# POV.net
KiCad netlist of a schematic drawn in EAGLE
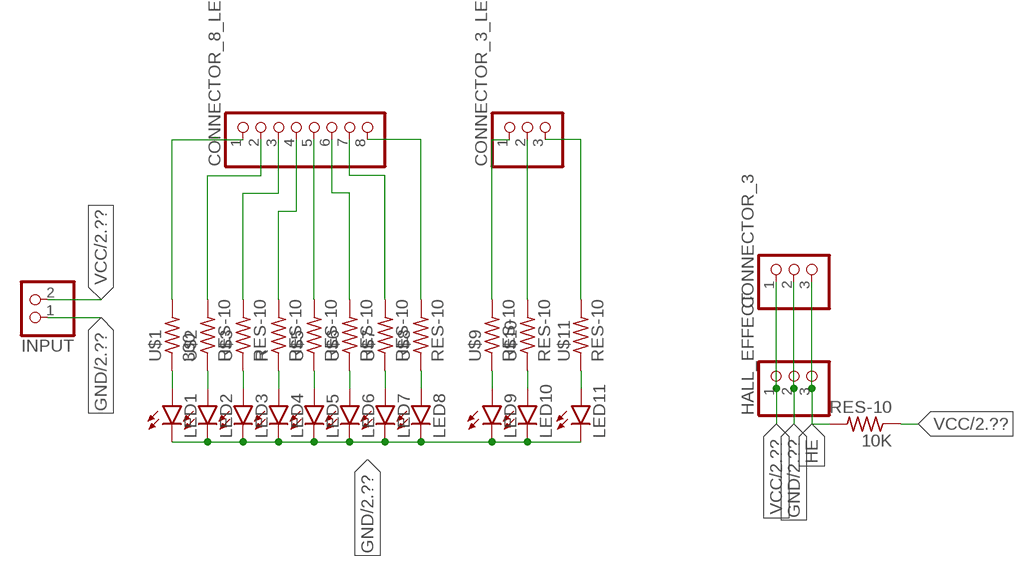
[diagram p0: schematic, sheet 1]
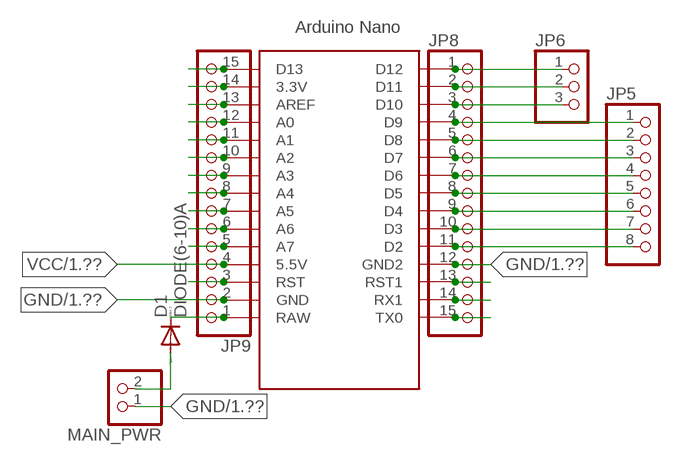
[diagram p1: schematic, sheet 2]

(export (version "E")
  (design (tool "Eeschema 10.0.6"))
  (components
    (comp (ref "D1")
      (value "DIODE(6-10)A")
      (footprint "eagle-import:DO201-15")
      (libsource (lib "eagle-import") (part "DIODE(6-10)A"))
    )
    (comp (ref "JP5")
      (value "PINHD-1X8")
      (footprint "eagle-import:1X08")
      (libsource (lib "eagle-import") (part "PINHD-1X8"))
    )
    (comp (ref "JP6")
      (value "PINHD-1X3")
      (footprint "eagle-import:1X03")
      (libsource (lib "eagle-import") (part "PINHD-1X3"))
    )
    (comp (ref "JP8")
      (value "PINHD-1X15")
      (footprint "eagle-import:1X15")
      (libsource (lib "eagle-import") (part "PINHD-1X15"))
    )
    (comp (ref "JP9")
      (value "PINHD-1X15")
      (footprint "eagle-import:1X15")
      (libsource (lib "eagle-import") (part "PINHD-1X15"))
    )
    (comp (ref "MAIN_PWR")
      (value "PINHD-1X2")
      (footprint "eagle-import:1X02")
      (libsource (lib "eagle-import") (part "PINHD-1X2"))
    )
    (comp (ref "U$12")
      (value "ARDUINO_NANO")
      (footprint "eagle-import:NANO")
      (libsource (lib "eagle-import") (part "ARDUINO_NANO"))
    )
    (comp (ref "10K")
      (value "RES-10")
      (footprint "eagle-import:0207_10")
      (libsource (lib "eagle-import") (part "RES-10"))
    )
    (comp (ref "CONNECTOR_3")
      (value "PINHD-1X3")
      (footprint "eagle-import:1X03")
      (libsource (lib "eagle-import") (part "pinhead_325_PINHD-1X3"))
    )
    (comp (ref "CONNECTOR_3_LED")
      (value "PINHD-1X3")
      (footprint "eagle-import:1X03")
      (libsource (lib "eagle-import") (part "pinhead_325_PINHD-1X3"))
    )
    (comp (ref "CONNECTOR_8_LED")
      (value "PINHD-1X8")
      (footprint "eagle-import:1X08")
      (libsource (lib "eagle-import") (part "pinhead_325_PINHD-1X8"))
    )
    (comp (ref "HALL_EFFECT")
      (value "PINHD-1X3")
      (footprint "eagle-import:1X03")
      (libsource (lib "eagle-import") (part "pinhead_325_PINHD-1X3"))
    )
    (comp (ref "INPUT")
      (value "PINHD-1X2")
      (footprint "eagle-import:1X02")
      (libsource (lib "eagle-import") (part "pinhead_325_PINHD-1X2"))
    )
    (comp (ref "LED1")
      (value "LED5MM")
      (footprint "eagle-import:LED5MM")
      (libsource (lib "eagle-import") (part "LED5MM"))
    )
    (comp (ref "LED2")
      (value "LED5MM")
      (footprint "eagle-import:LED5MM")
      (libsource (lib "eagle-import") (part "LED5MM"))
    )
    (comp (ref "LED3")
      (value "LED5MM")
      (footprint "eagle-import:LED5MM")
      (libsource (lib "eagle-import") (part "LED5MM"))
    )
    (comp (ref "LED4")
      (value "LED5MM")
      (footprint "eagle-import:LED5MM")
      (libsource (lib "eagle-import") (part "LED5MM"))
    )
    (comp (ref "LED5")
      (value "LED5MM")
      (footprint "eagle-import:LED5MM")
      (libsource (lib "eagle-import") (part "LED5MM"))
    )
    (comp (ref "LED6")
      (value "LED5MM")
      (footprint "eagle-import:LED5MM")
      (libsource (lib "eagle-import") (part "LED5MM"))
    )
    (comp (ref "LED7")
      (value "LED5MM")
      (footprint "eagle-import:LED5MM")
      (libsource (lib "eagle-import") (part "LED5MM"))
    )
    (comp (ref "LED8")
      (value "LED5MM")
      (footprint "eagle-import:LED5MM")
      (libsource (lib "eagle-import") (part "LED5MM"))
    )
    (comp (ref "LED9")
      (value "LED5MM")
      (footprint "eagle-import:LED5MM")
      (libsource (lib "eagle-import") (part "LED5MM"))
    )
    (comp (ref "LED10")
      (value "LED5MM")
      (footprint "eagle-import:LED5MM")
      (libsource (lib "eagle-import") (part "LED5MM"))
    )
    (comp (ref "LED11")
      (value "LED5MM")
      (footprint "eagle-import:LED5MM")
      (libsource (lib "eagle-import") (part "LED5MM"))
    )
    (comp (ref "R")
      (value "RES-10")
      (footprint "eagle-import:0207_10")
      (libsource (lib "eagle-import") (part "RES-10"))
    )
    (comp (ref "U$1")
      (value "330")
      (footprint "eagle-import:0207_10")
      (libsource (lib "eagle-import") (part "RES-10"))
    )
    (comp (ref "U$2")
      (value "RES-10")
      (footprint "eagle-import:0207_10")
      (libsource (lib "eagle-import") (part "RES-10"))
    )
    (comp (ref "U$3")
      (value "RES-10")
      (footprint "eagle-import:0207_10")
      (libsource (lib "eagle-import") (part "RES-10"))
    )
    (comp (ref "U$5")
      (value "RES-10")
      (footprint "eagle-import:0207_10")
      (libsource (lib "eagle-import") (part "RES-10"))
    )
    (comp (ref "U$6")
      (value "RES-10")
      (footprint "eagle-import:0207_10")
      (libsource (lib "eagle-import") (part "RES-10"))
    )
    (comp (ref "U$7")
      (value "RES-10")
      (footprint "eagle-import:0207_10")
      (libsource (lib "eagle-import") (part "RES-10"))
    )
    (comp (ref "U$8")
      (value "RES-10")
      (footprint "eagle-import:0207_10")
      (libsource (lib "eagle-import") (part "RES-10"))
    )
    (comp (ref "U$9")
      (value "RES-10")
      (footprint "eagle-import:0207_10")
      (libsource (lib "eagle-import") (part "RES-10"))
    )
    (comp (ref "U$10")
      (value "RES-10")
      (footprint "eagle-import:0207_10")
      (libsource (lib "eagle-import") (part "RES-10"))
    )
    (comp (ref "U$11")
      (value "RES-10")
      (footprint "eagle-import:0207_10")
      (libsource (lib "eagle-import") (part "RES-10"))
    )
  )
  (nets
    (net (code "1") (name "GND") (class "Default")
      (node (ref "CONNECTOR_3") (pin "2") (pinfunction "2_2") (pintype "passive"))
      (node (ref "HALL_EFFECT") (pin "2") (pinfunction "2_2") (pintype "passive"))
      (node (ref "INPUT") (pin "1") (pinfunction "1_1") (pintype "passive"))
      (node (ref "JP8") (pin "12") (pinfunction "12_12") (pintype "passive"))
      (node (ref "JP9") (pin "2") (pinfunction "2_2") (pintype "passive"))
      (node (ref "LED1") (pin "K") (pinfunction "C_K") (pintype "passive"))
      (node (ref "LED10") (pin "K") (pinfunction "C_K") (pintype "passive"))
      (node (ref "LED11") (pin "K") (pinfunction "C_K") (pintype "passive"))
      (node (ref "LED2") (pin "K") (pinfunction "C_K") (pintype "passive"))
      (node (ref "LED3") (pin "K") (pinfunction "C_K") (pintype "passive"))
      (node (ref "LED4") (pin "K") (pinfunction "C_K") (pintype "passive"))
      (node (ref "LED5") (pin "K") (pinfunction "C_K") (pintype "passive"))
      (node (ref "LED6") (pin "K") (pinfunction "C_K") (pintype "passive"))
      (node (ref "LED7") (pin "K") (pinfunction "C_K") (pintype "passive"))
      (node (ref "LED8") (pin "K") (pinfunction "C_K") (pintype "passive"))
      (node (ref "LED9") (pin "K") (pinfunction "C_K") (pintype "passive"))
      (node (ref "MAIN_PWR") (pin "1") (pinfunction "1_1") (pintype "passive"))
      (node (ref "U$12") (pin "GND") (pinfunction "GND_GND") (pintype "bidirectional"))
      (node (ref "U$12") (pin "GND1") (pinfunction "GND2_GND1") (pintype "bidirectional"))
    )
    (net (code "2") (name "HE") (class "Default")
      (node (ref "10K") (pin "2") (pinfunction "2_2") (pintype "passive"))
      (node (ref "CONNECTOR_3") (pin "3") (pinfunction "3_3") (pintype "passive"))
      (node (ref "HALL_EFFECT") (pin "3") (pinfunction "3_3") (pintype "passive"))
    )
    (net (code "3") (name "Net-(CONNECTOR_3_LED-Pad1)") (class "Default")
      (node (ref "CONNECTOR_3_LED") (pin "1") (pinfunction "1_1") (pintype "passive"))
      (node (ref "U$9") (pin "2") (pinfunction "2_2") (pintype "passive"))
    )
    (net (code "4") (name "Net-(CONNECTOR_3_LED-Pad2)") (class "Default")
      (node (ref "CONNECTOR_3_LED") (pin "2") (pinfunction "2_2") (pintype "passive"))
      (node (ref "U$10") (pin "2") (pinfunction "2_2") (pintype "passive"))
    )
    (net (code "5") (name "Net-(CONNECTOR_3_LED-Pad3)") (class "Default")
      (node (ref "CONNECTOR_3_LED") (pin "3") (pinfunction "3_3") (pintype "passive"))
      (node (ref "U$11") (pin "2") (pinfunction "2_2") (pintype "passive"))
    )
    (net (code "6") (name "Net-(CONNECTOR_8_LED-Pad1)") (class "Default")
      (node (ref "CONNECTOR_8_LED") (pin "1") (pinfunction "1_1") (pintype "passive"))
      (node (ref "U$1") (pin "2") (pinfunction "2_2") (pintype "passive"))
    )
    (net (code "7") (name "Net-(CONNECTOR_8_LED-Pad2)") (class "Default")
      (node (ref "CONNECTOR_8_LED") (pin "2") (pinfunction "2_2") (pintype "passive"))
      (node (ref "U$2") (pin "2") (pinfunction "2_2") (pintype "passive"))
    )
    (net (code "8") (name "Net-(CONNECTOR_8_LED-Pad3)") (class "Default")
      (node (ref "CONNECTOR_8_LED") (pin "3") (pinfunction "3_3") (pintype "passive"))
      (node (ref "U$3") (pin "2") (pinfunction "2_2") (pintype "passive"))
    )
    (net (code "9") (name "Net-(CONNECTOR_8_LED-Pad4)") (class "Default")
      (node (ref "CONNECTOR_8_LED") (pin "4") (pinfunction "4_4") (pintype "passive"))
      (node (ref "R") (pin "2") (pinfunction "2_2") (pintype "passive"))
    )
    (net (code "10") (name "Net-(CONNECTOR_8_LED-Pad5)") (class "Default")
      (node (ref "CONNECTOR_8_LED") (pin "5") (pinfunction "5_5") (pintype "passive"))
      (node (ref "U$5") (pin "2") (pinfunction "2_2") (pintype "passive"))
    )
    (net (code "11") (name "Net-(CONNECTOR_8_LED-Pad6)") (class "Default")
      (node (ref "CONNECTOR_8_LED") (pin "6") (pinfunction "6_6") (pintype "passive"))
      (node (ref "U$6") (pin "2") (pinfunction "2_2") (pintype "passive"))
    )
    (net (code "12") (name "Net-(CONNECTOR_8_LED-Pad7)") (class "Default")
      (node (ref "CONNECTOR_8_LED") (pin "7") (pinfunction "7_7") (pintype "passive"))
      (node (ref "U$7") (pin "2") (pinfunction "2_2") (pintype "passive"))
    )
    (net (code "13") (name "Net-(CONNECTOR_8_LED-Pad8)") (class "Default")
      (node (ref "CONNECTOR_8_LED") (pin "8") (pinfunction "8_8") (pintype "passive"))
      (node (ref "U$8") (pin "2") (pinfunction "2_2") (pintype "passive"))
    )
    (net (code "14") (name "Net-(D1-PadA)") (class "Default")
      (node (ref "D1") (pin "A") (pinfunction "A_A") (pintype "passive"))
      (node (ref "MAIN_PWR") (pin "2") (pinfunction "2_2") (pintype "passive"))
    )
    (net (code "15") (name "Net-(D1-PadC)") (class "Default")
      (node (ref "D1") (pin "C") (pinfunction "C_C") (pintype "passive"))
      (node (ref "JP9") (pin "1") (pinfunction "1_1") (pintype "passive"))
      (node (ref "U$12") (pin "RAW") (pinfunction "RAW_RAW") (pintype "bidirectional"))
    )
    (net (code "16") (name "Net-(JP5-Pad1)") (class "Default")
      (node (ref "JP5") (pin "1") (pinfunction "1_1") (pintype "passive"))
      (node (ref "JP8") (pin "4") (pinfunction "4_4") (pintype "passive"))
      (node (ref "U$12") (pin "D9") (pinfunction "D9_D9") (pintype "bidirectional"))
    )
    (net (code "17") (name "Net-(JP5-Pad2)") (class "Default")
      (node (ref "JP5") (pin "2") (pinfunction "2_2") (pintype "passive"))
      (node (ref "JP8") (pin "5") (pinfunction "5_5") (pintype "passive"))
      (node (ref "U$12") (pin "D8") (pinfunction "D8_D8") (pintype "bidirectional"))
    )
    (net (code "18") (name "Net-(JP5-Pad3)") (class "Default")
      (node (ref "JP5") (pin "3") (pinfunction "3_3") (pintype "passive"))
      (node (ref "JP8") (pin "6") (pinfunction "6_6") (pintype "passive"))
      (node (ref "U$12") (pin "D7") (pinfunction "D7_D7") (pintype "bidirectional"))
    )
    (net (code "19") (name "Net-(JP5-Pad4)") (class "Default")
      (node (ref "JP5") (pin "4") (pinfunction "4_4") (pintype "passive"))
      (node (ref "JP8") (pin "7") (pinfunction "7_7") (pintype "passive"))
      (node (ref "U$12") (pin "D6") (pinfunction "D6_D6") (pintype "bidirectional"))
    )
    (net (code "20") (name "Net-(JP5-Pad5)") (class "Default")
      (node (ref "JP5") (pin "5") (pinfunction "5_5") (pintype "passive"))
      (node (ref "JP8") (pin "8") (pinfunction "8_8") (pintype "passive"))
      (node (ref "U$12") (pin "D5") (pinfunction "D5_D5") (pintype "bidirectional"))
    )
    (net (code "21") (name "Net-(JP5-Pad6)") (class "Default")
      (node (ref "JP5") (pin "6") (pinfunction "6_6") (pintype "passive"))
      (node (ref "JP8") (pin "9") (pinfunction "9_9") (pintype "passive"))
      (node (ref "U$12") (pin "D4") (pinfunction "D4_D4") (pintype "bidirectional"))
    )
    (net (code "22") (name "Net-(JP5-Pad7)") (class "Default")
      (node (ref "JP5") (pin "7") (pinfunction "7_7") (pintype "passive"))
      (node (ref "JP8") (pin "10") (pinfunction "10_10") (pintype "passive"))
      (node (ref "U$12") (pin "D3") (pinfunction "D3_D3") (pintype "bidirectional"))
    )
    (net (code "23") (name "Net-(JP5-Pad8)") (class "Default")
      (node (ref "JP5") (pin "8") (pinfunction "8_8") (pintype "passive"))
      (node (ref "JP8") (pin "11") (pinfunction "11_11") (pintype "passive"))
      (node (ref "U$12") (pin "D2") (pinfunction "D2_D2") (pintype "bidirectional"))
    )
    (net (code "24") (name "Net-(JP6-Pad1)") (class "Default")
      (node (ref "JP6") (pin "1") (pinfunction "1_1") (pintype "passive"))
      (node (ref "JP8") (pin "1") (pinfunction "1_1") (pintype "passive"))
      (node (ref "U$12") (pin "D12") (pinfunction "D12_D12") (pintype "bidirectional"))
    )
    (net (code "25") (name "Net-(JP6-Pad2)") (class "Default")
      (node (ref "JP6") (pin "2") (pinfunction "2_2") (pintype "passive"))
      (node (ref "JP8") (pin "2") (pinfunction "2_2") (pintype "passive"))
      (node (ref "U$12") (pin "D11") (pinfunction "D11_D11") (pintype "bidirectional"))
    )
    (net (code "26") (name "Net-(JP6-Pad3)") (class "Default")
      (node (ref "JP6") (pin "3") (pinfunction "3_3") (pintype "passive"))
      (node (ref "JP8") (pin "3") (pinfunction "3_3") (pintype "passive"))
      (node (ref "U$12") (pin "D10") (pinfunction "D10_D10") (pintype "bidirectional"))
    )
    (net (code "27") (name "Net-(JP8-Pad13)") (class "Default")
      (node (ref "JP8") (pin "13") (pinfunction "13_13") (pintype "passive"))
      (node (ref "U$12") (pin "RST1") (pinfunction "RST1_RST1") (pintype "bidirectional"))
    )
    (net (code "28") (name "Net-(JP8-Pad14)") (class "Default")
      (node (ref "JP8") (pin "14") (pinfunction "14_14") (pintype "passive"))
      (node (ref "U$12") (pin "RX1") (pinfunction "RX1_RX1") (pintype "bidirectional"))
    )
    (net (code "29") (name "Net-(JP8-Pad15)") (class "Default")
      (node (ref "JP8") (pin "15") (pinfunction "15_15") (pintype "passive"))
      (node (ref "U$12") (pin "TX0") (pinfunction "TX0_TX0") (pintype "bidirectional"))
    )
    (net (code "30") (name "Net-(JP9-Pad3)") (class "Default")
      (node (ref "JP9") (pin "3") (pinfunction "3_3") (pintype "passive"))
      (node (ref "U$12") (pin "RST") (pinfunction "RST_RST") (pintype "bidirectional"))
    )
    (net (code "31") (name "Net-(JP9-Pad5)") (class "Default")
      (node (ref "JP9") (pin "5") (pinfunction "5_5") (pintype "passive"))
      (node (ref "U$12") (pin "A7") (pinfunction "A7_A7") (pintype "bidirectional"))
    )
    (net (code "32") (name "Net-(JP9-Pad6)") (class "Default")
      (node (ref "JP9") (pin "6") (pinfunction "6_6") (pintype "passive"))
      (node (ref "U$12") (pin "A6") (pinfunction "A6_A6") (pintype "bidirectional"))
    )
    (net (code "33") (name "Net-(JP9-Pad7)") (class "Default")
      (node (ref "JP9") (pin "7") (pinfunction "7_7") (pintype "passive"))
      (node (ref "U$12") (pin "A5") (pinfunction "A5_A5") (pintype "bidirectional"))
    )
    (net (code "34") (name "Net-(JP9-Pad8)") (class "Default")
      (node (ref "JP9") (pin "8") (pinfunction "8_8") (pintype "passive"))
      (node (ref "U$12") (pin "A4") (pinfunction "A4_A4") (pintype "bidirectional"))
    )
    (net (code "35") (name "Net-(JP9-Pad9)") (class "Default")
      (node (ref "JP9") (pin "9") (pinfunction "9_9") (pintype "passive"))
      (node (ref "U$12") (pin "A3") (pinfunction "A3_A3") (pintype "bidirectional"))
    )
    (net (code "36") (name "Net-(JP9-Pad10)") (class "Default")
      (node (ref "JP9") (pin "10") (pinfunction "10_10") (pintype "passive"))
      (node (ref "U$12") (pin "A2") (pinfunction "A2_A2") (pintype "bidirectional"))
    )
    (net (code "37") (name "Net-(JP9-Pad11)") (class "Default")
      (node (ref "JP9") (pin "11") (pinfunction "11_11") (pintype "passive"))
      (node (ref "U$12") (pin "A1") (pinfunction "A1_A1") (pintype "bidirectional"))
    )
    (net (code "38") (name "Net-(JP9-Pad12)") (class "Default")
      (node (ref "JP9") (pin "12") (pinfunction "12_12") (pintype "passive"))
      (node (ref "U$12") (pin "A0") (pinfunction "A0_A0") (pintype "bidirectional"))
    )
    (net (code "39") (name "Net-(JP9-Pad13)") (class "Default")
      (node (ref "JP9") (pin "13") (pinfunction "13_13") (pintype "passive"))
      (node (ref "U$12") (pin "AREF") (pinfunction "AREF_AREF") (pintype "bidirectional"))
    )
    (net (code "40") (name "Net-(JP9-Pad14)") (class "Default")
      (node (ref "JP9") (pin "14") (pinfunction "14_14") (pintype "passive"))
      (node (ref "U$12") (pin "3.3V") (pinfunction "3.3V_3.3V") (pintype "bidirectional"))
    )
    (net (code "41") (name "Net-(JP9-Pad15)") (class "Default")
      (node (ref "JP9") (pin "15") (pinfunction "15_15") (pintype "passive"))
      (node (ref "U$12") (pin "D13") (pinfunction "D13_D13") (pintype "bidirectional"))
    )
    (net (code "42") (name "Net-(LED1-PadA)") (class "Default")
      (node (ref "LED1") (pin "A") (pinfunction "A_A") (pintype "passive"))
      (node (ref "U$1") (pin "1") (pinfunction "1_1") (pintype "passive"))
    )
    (net (code "43") (name "Net-(LED2-PadA)") (class "Default")
      (node (ref "LED2") (pin "A") (pinfunction "A_A") (pintype "passive"))
      (node (ref "U$2") (pin "1") (pinfunction "1_1") (pintype "passive"))
    )
    (net (code "44") (name "Net-(LED3-PadA)") (class "Default")
      (node (ref "LED3") (pin "A") (pinfunction "A_A") (pintype "passive"))
      (node (ref "U$3") (pin "1") (pinfunction "1_1") (pintype "passive"))
    )
    (net (code "45") (name "Net-(LED4-PadA)") (class "Default")
      (node (ref "LED4") (pin "A") (pinfunction "A_A") (pintype "passive"))
      (node (ref "R") (pin "1") (pinfunction "1_1") (pintype "passive"))
    )
    (net (code "46") (name "Net-(LED5-PadA)") (class "Default")
      (node (ref "LED5") (pin "A") (pinfunction "A_A") (pintype "passive"))
      (node (ref "U$5") (pin "1") (pinfunction "1_1") (pintype "passive"))
    )
    (net (code "47") (name "Net-(LED6-PadA)") (class "Default")
      (node (ref "LED6") (pin "A") (pinfunction "A_A") (pintype "passive"))
      (node (ref "U$6") (pin "1") (pinfunction "1_1") (pintype "passive"))
    )
    (net (code "48") (name "Net-(LED7-PadA)") (class "Default")
      (node (ref "LED7") (pin "A") (pinfunction "A_A") (pintype "passive"))
      (node (ref "U$7") (pin "1") (pinfunction "1_1") (pintype "passive"))
    )
    (net (code "49") (name "Net-(LED8-PadA)") (class "Default")
      (node (ref "LED8") (pin "A") (pinfunction "A_A") (pintype "passive"))
      (node (ref "U$8") (pin "1") (pinfunction "1_1") (pintype "passive"))
    )
    (net (code "50") (name "Net-(LED9-PadA)") (class "Default")
      (node (ref "LED9") (pin "A") (pinfunction "A_A") (pintype "passive"))
      (node (ref "U$9") (pin "1") (pinfunction "1_1") (pintype "passive"))
    )
    (net (code "51") (name "Net-(LED10-PadA)") (class "Default")
      (node (ref "LED10") (pin "A") (pinfunction "A_A") (pintype "passive"))
      (node (ref "U$10") (pin "1") (pinfunction "1_1") (pintype "passive"))
    )
    (net (code "52") (name "Net-(LED11-PadA)") (class "Default")
      (node (ref "LED11") (pin "A") (pinfunction "A_A") (pintype "passive"))
      (node (ref "U$11") (pin "1") (pinfunction "1_1") (pintype "passive"))
    )
    (net (code "53") (name "VCC") (class "Default")
      (node (ref "10K") (pin "1") (pinfunction "1_1") (pintype "passive"))
      (node (ref "CONNECTOR_3") (pin "1") (pinfunction "1_1") (pintype "passive"))
      (node (ref "HALL_EFFECT") (pin "1") (pinfunction "1_1") (pintype "passive"))
      (node (ref "INPUT") (pin "2") (pinfunction "2_2") (pintype "passive"))
      (node (ref "JP9") (pin "4") (pinfunction "4_4") (pintype "passive"))
      (node (ref "U$12") (pin "5V") (pinfunction "5.5V_5V") (pintype "bidirectional"))
    )
  )
)
